# SCH_PCB-micropad_2024-07-07.net
KiCad netlist of a schematic drawn in EasyEDA
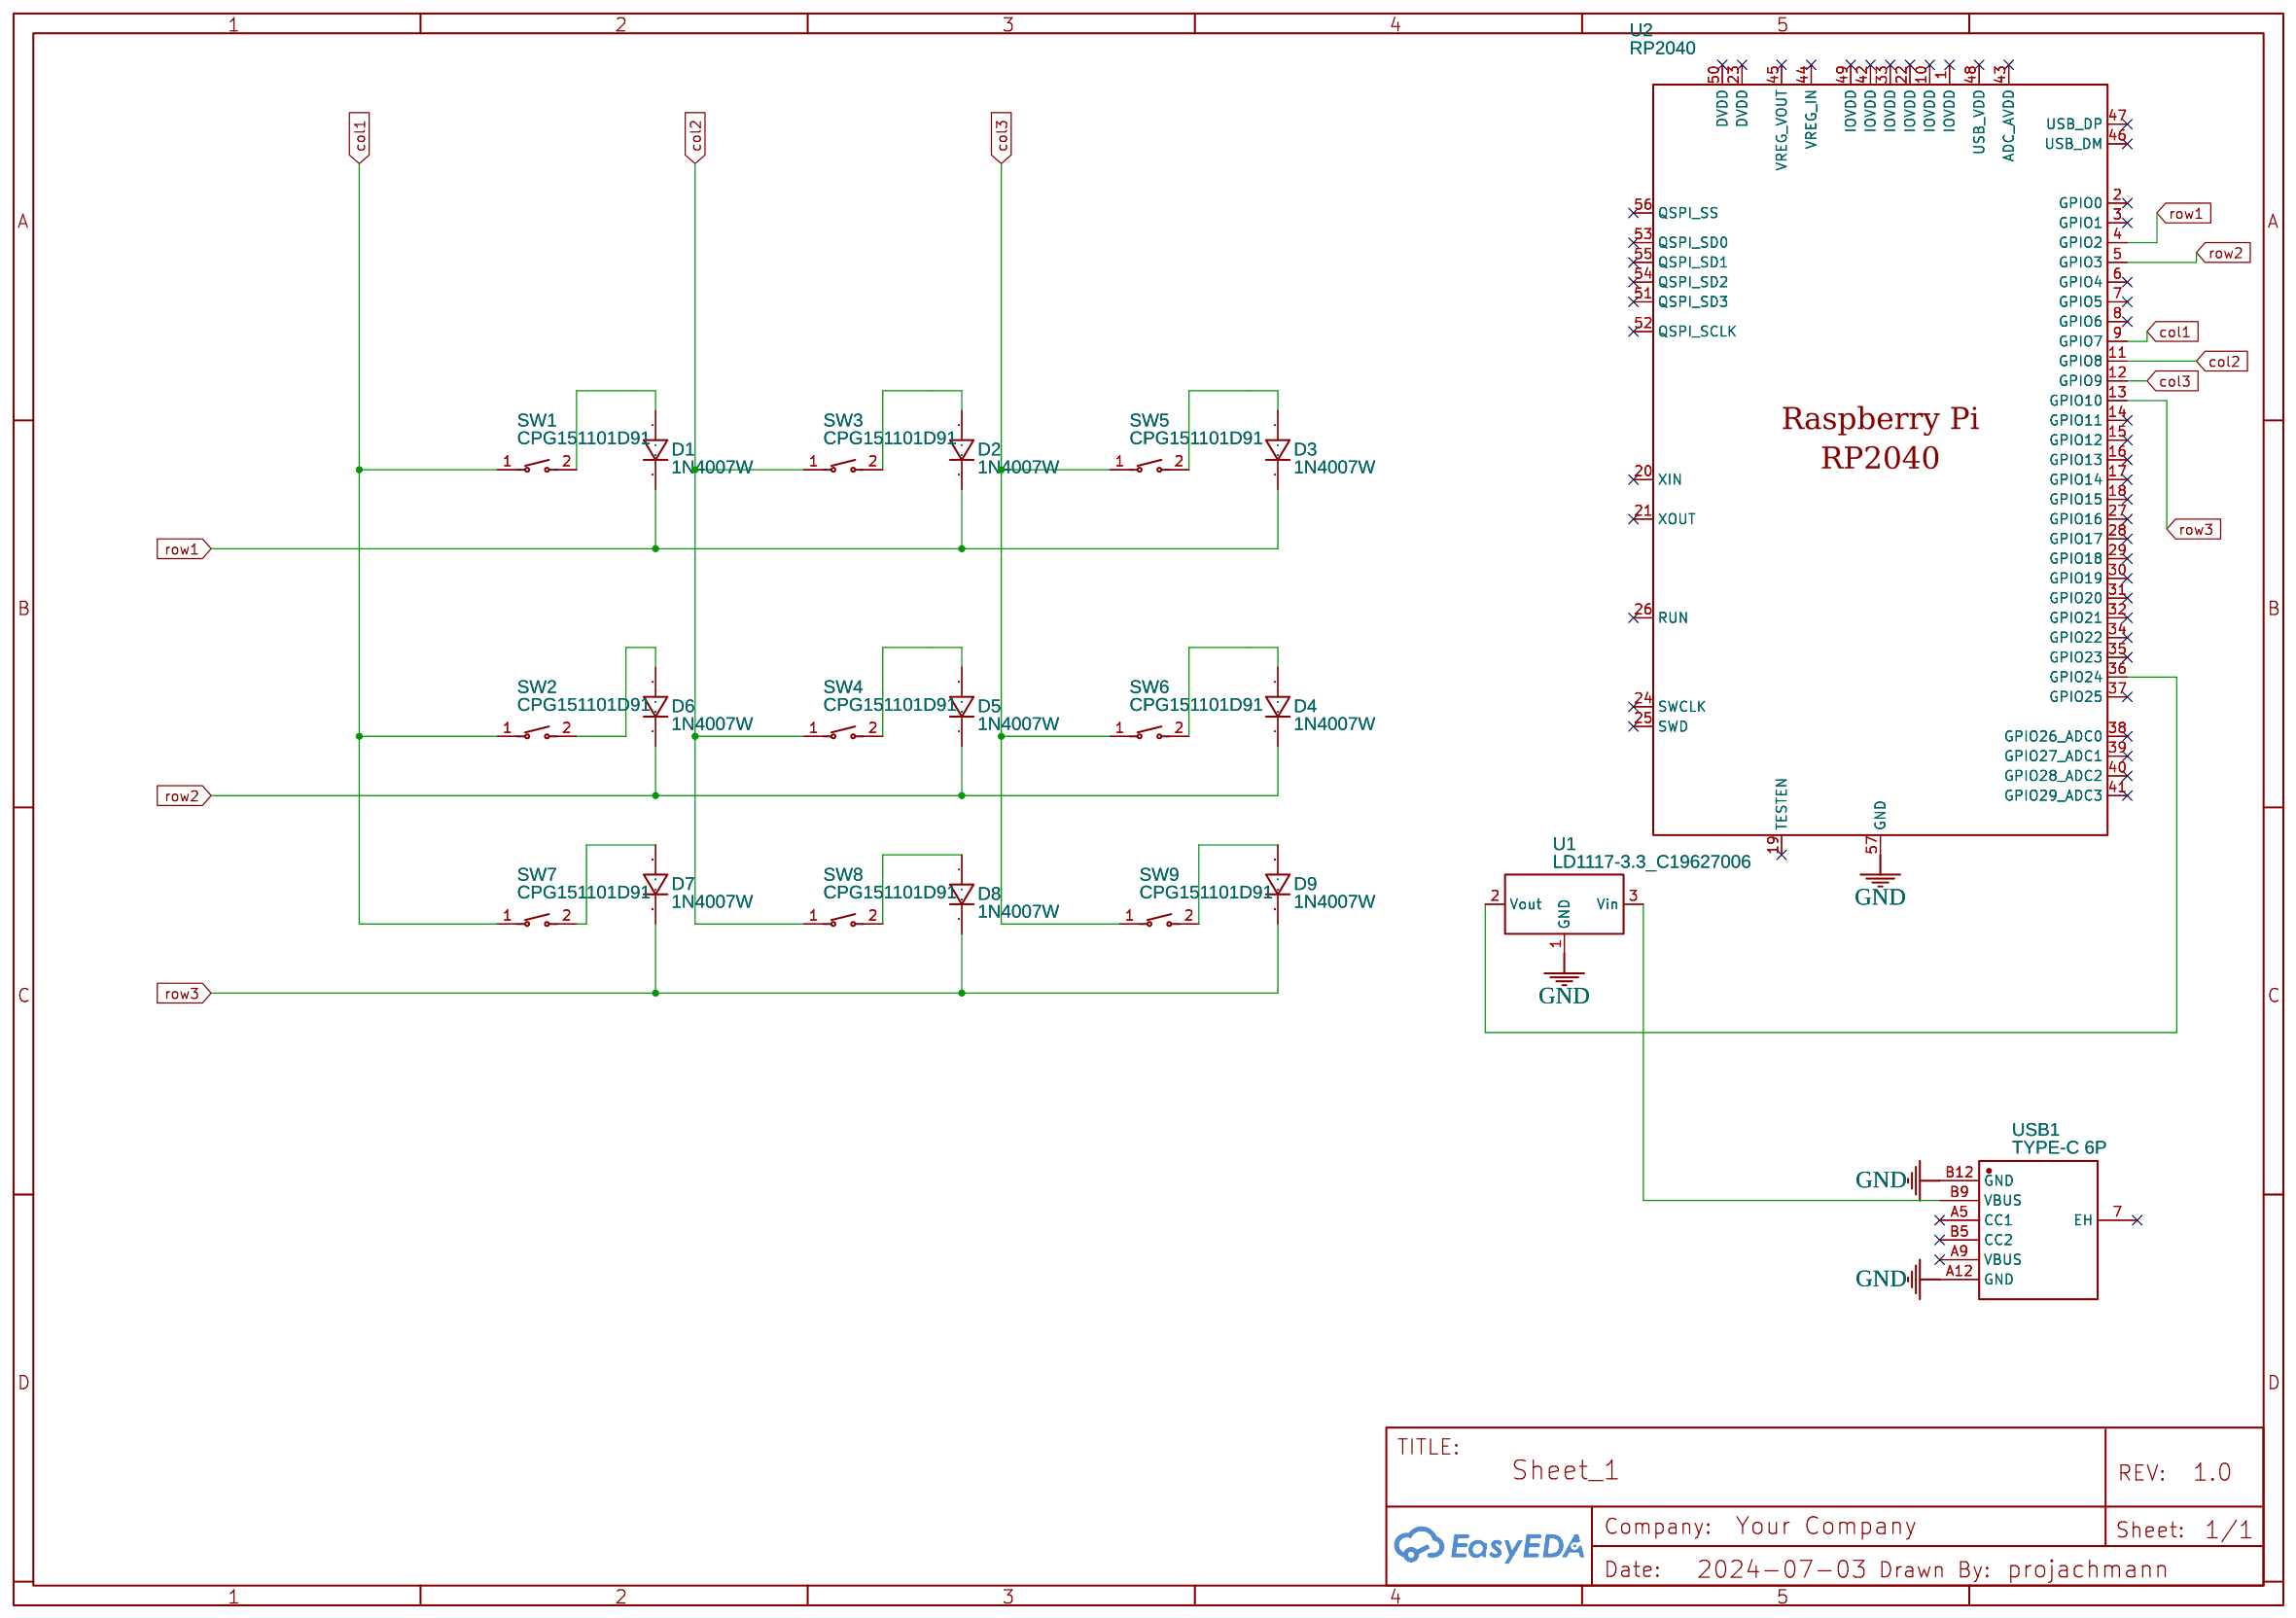
[diagram p0: schematic sheet]

(export (version "E")
  (design (tool "Eeschema 10.0.6"))
  (components
    (comp (ref "D1")
      (value "1N4007W")
      (fields (field (name "Manufacturer") "BLUE ROCKET"))
      (libsource (lib "") (part "1N4007W"))
    )
    (comp (ref "D2")
      (value "1N4007W")
      (fields (field (name "Manufacturer") "BLUE ROCKET"))
      (libsource (lib "") (part "1N4007W"))
    )
    (comp (ref "D3")
      (value "1N4007W")
      (fields (field (name "Manufacturer") "BLUE ROCKET"))
      (libsource (lib "") (part "1N4007W"))
    )
    (comp (ref "D4")
      (value "1N4007W")
      (fields (field (name "Manufacturer") "BLUE ROCKET"))
      (libsource (lib "") (part "1N4007W"))
    )
    (comp (ref "D5")
      (value "1N4007W")
      (fields (field (name "Manufacturer") "BLUE ROCKET"))
      (libsource (lib "") (part "1N4007W"))
    )
    (comp (ref "D6")
      (value "1N4007W")
      (fields (field (name "Manufacturer") "BLUE ROCKET"))
      (libsource (lib "") (part "1N4007W"))
    )
    (comp (ref "D7")
      (value "1N4007W")
      (fields (field (name "Manufacturer") "BLUE ROCKET"))
      (libsource (lib "") (part "1N4007W"))
    )
    (comp (ref "D8")
      (value "1N4007W")
      (fields (field (name "Manufacturer") "BLUE ROCKET"))
      (libsource (lib "") (part "1N4007W"))
    )
    (comp (ref "D9")
      (value "1N4007W")
      (fields (field (name "Manufacturer") "BLUE ROCKET"))
      (libsource (lib "") (part "1N4007W"))
    )
    (comp (ref "SW1")
      (value "CPG151101D91")
      (fields (field (name "Manufacturer") "Kailh(凯华)"))
      (libsource (lib "") (part "CPG151101D91"))
    )
    (comp (ref "SW2")
      (value "CPG151101D91")
      (fields (field (name "Manufacturer") "Kailh(凯华)"))
      (libsource (lib "") (part "CPG151101D91"))
    )
    (comp (ref "SW3")
      (value "CPG151101D91")
      (fields (field (name "Manufacturer") "Kailh(凯华)"))
      (libsource (lib "") (part "CPG151101D91"))
    )
    (comp (ref "SW4")
      (value "CPG151101D91")
      (fields (field (name "Manufacturer") "Kailh(凯华)"))
      (libsource (lib "") (part "CPG151101D91"))
    )
    (comp (ref "SW5")
      (value "CPG151101D91")
      (fields (field (name "Manufacturer") "Kailh(凯华)"))
      (libsource (lib "") (part "CPG151101D91"))
    )
    (comp (ref "SW6")
      (value "CPG151101D91")
      (fields (field (name "Manufacturer") "Kailh(凯华)"))
      (libsource (lib "") (part "CPG151101D91"))
    )
    (comp (ref "SW7")
      (value "CPG151101D91")
      (fields (field (name "Manufacturer") "Kailh(凯华)"))
      (libsource (lib "") (part "CPG151101D91"))
    )
    (comp (ref "SW8")
      (value "CPG151101D91")
      (fields (field (name "Manufacturer") "Kailh(凯华)"))
      (libsource (lib "") (part "CPG151101D91"))
    )
    (comp (ref "SW9")
      (value "CPG151101D91")
      (fields (field (name "Manufacturer") "Kailh(凯华)"))
      (libsource (lib "") (part "CPG151101D91"))
    )
    (comp (ref "U1")
      (value "LD1117-3.3_C19627006")
      (fields
        (field (name "Manufacturer Part") "LD1117-3.3")
        (field (name "Manufacturer") "HXY MOSFET(华轩阳电子)")
      )
      (libsource (lib "") (part "LD1117-3.3_C19627006"))
    )
    (comp (ref "U2")
      (value "RP2040")
      (fields (field (name "Manufacturer") "Raspberry Pi(树莓派)"))
      (libsource (lib "") (part "RP2040"))
    )
    (comp (ref "USB1")
      (value "TYPE-C 6P")
      (fields (field (name "Manufacturer") "SHOU HAN(首韩)"))
      (libsource (lib "") (part "TYPE-C 6P"))
    )
  )
  (nets
    (net (code "1") (name "GND") (class "Default")
      (node (ref "U1") (pin "1") (pinfunction "GND_1") (pintype "unspecified"))
      (node (ref "U2") (pin "57") (pinfunction "GND_57") (pintype "bidirectional"))
      (node (ref "USB1") (pin "A12") (pinfunction "GND_A12") (pintype "unspecified"))
      (node (ref "USB1") (pin "B12") (pinfunction "GND_B12") (pintype "unspecified"))
    )
    (net (code "2") (name "Net-(D1-Pad2)") (class "Default")
      (node (ref "D1") (pin "2") (pinfunction "2_2") (pintype "unspecified"))
      (node (ref "SW1") (pin "2") (pinfunction "2_2") (pintype "unspecified"))
    )
    (net (code "3") (name "Net-(D2-Pad2)") (class "Default")
      (node (ref "D2") (pin "2") (pinfunction "2_2") (pintype "unspecified"))
      (node (ref "SW3") (pin "2") (pinfunction "2_2") (pintype "unspecified"))
    )
    (net (code "4") (name "Net-(D3-Pad2)") (class "Default")
      (node (ref "D3") (pin "2") (pinfunction "2_2") (pintype "unspecified"))
      (node (ref "SW5") (pin "2") (pinfunction "2_2") (pintype "unspecified"))
    )
    (net (code "5") (name "Net-(D4-Pad2)") (class "Default")
      (node (ref "D4") (pin "2") (pinfunction "2_2") (pintype "unspecified"))
      (node (ref "SW6") (pin "2") (pinfunction "2_2") (pintype "unspecified"))
    )
    (net (code "6") (name "Net-(D5-Pad2)") (class "Default")
      (node (ref "D5") (pin "2") (pinfunction "2_2") (pintype "unspecified"))
      (node (ref "SW4") (pin "2") (pinfunction "2_2") (pintype "unspecified"))
    )
    (net (code "7") (name "Net-(D6-Pad2)") (class "Default")
      (node (ref "D6") (pin "2") (pinfunction "2_2") (pintype "unspecified"))
      (node (ref "SW2") (pin "2") (pinfunction "2_2") (pintype "unspecified"))
    )
    (net (code "8") (name "Net-(D7-Pad2)") (class "Default")
      (node (ref "D7") (pin "2") (pinfunction "2_2") (pintype "unspecified"))
      (node (ref "SW7") (pin "2") (pinfunction "2_2") (pintype "unspecified"))
    )
    (net (code "9") (name "Net-(D8-Pad2)") (class "Default")
      (node (ref "D8") (pin "2") (pinfunction "2_2") (pintype "unspecified"))
      (node (ref "SW8") (pin "2") (pinfunction "2_2") (pintype "unspecified"))
    )
    (net (code "10") (name "Net-(D9-Pad2)") (class "Default")
      (node (ref "D9") (pin "2") (pinfunction "2_2") (pintype "unspecified"))
      (node (ref "SW9") (pin "2") (pinfunction "2_2") (pintype "unspecified"))
    )
    (net (code "11") (name "Net-(U1-Vin)") (class "Default")
      (node (ref "U1") (pin "3") (pinfunction "Vin_3") (pintype "unspecified"))
      (node (ref "USB1") (pin "B9") (pinfunction "VBUS_B9") (pintype "unspecified"))
    )
    (net (code "12") (name "Net-(U1-Vout)") (class "Default")
      (node (ref "U1") (pin "2") (pinfunction "Vout_2") (pintype "unspecified"))
      (node (ref "U2") (pin "36") (pinfunction "GPIO24_36") (pintype "bidirectional"))
    )
    (net (code "13") (name "col1") (class "Default")
      (node (ref "SW1") (pin "1") (pinfunction "1_1") (pintype "unspecified"))
      (node (ref "SW2") (pin "1") (pinfunction "1_1") (pintype "unspecified"))
      (node (ref "SW7") (pin "1") (pinfunction "1_1") (pintype "unspecified"))
      (node (ref "U2") (pin "9") (pinfunction "GPIO7_9") (pintype "bidirectional"))
    )
    (net (code "14") (name "col2") (class "Default")
      (node (ref "SW3") (pin "1") (pinfunction "1_1") (pintype "unspecified"))
      (node (ref "SW4") (pin "1") (pinfunction "1_1") (pintype "unspecified"))
      (node (ref "SW8") (pin "1") (pinfunction "1_1") (pintype "unspecified"))
      (node (ref "U2") (pin "11") (pinfunction "GPIO8_11") (pintype "bidirectional"))
    )
    (net (code "15") (name "col3") (class "Default")
      (node (ref "SW5") (pin "1") (pinfunction "1_1") (pintype "unspecified"))
      (node (ref "SW6") (pin "1") (pinfunction "1_1") (pintype "unspecified"))
      (node (ref "SW9") (pin "1") (pinfunction "1_1") (pintype "unspecified"))
      (node (ref "U2") (pin "12") (pinfunction "GPIO9_12") (pintype "bidirectional"))
    )
    (net (code "16") (name "row1") (class "Default")
      (node (ref "D1") (pin "1") (pinfunction "1_1") (pintype "unspecified"))
      (node (ref "D2") (pin "1") (pinfunction "1_1") (pintype "unspecified"))
      (node (ref "D3") (pin "1") (pinfunction "1_1") (pintype "unspecified"))
      (node (ref "U2") (pin "4") (pinfunction "GPIO2_4") (pintype "bidirectional"))
    )
    (net (code "17") (name "row2") (class "Default")
      (node (ref "D4") (pin "1") (pinfunction "1_1") (pintype "unspecified"))
      (node (ref "D5") (pin "1") (pinfunction "1_1") (pintype "unspecified"))
      (node (ref "D6") (pin "1") (pinfunction "1_1") (pintype "unspecified"))
      (node (ref "U2") (pin "5") (pinfunction "GPIO3_5") (pintype "bidirectional"))
    )
    (net (code "18") (name "row3") (class "Default")
      (node (ref "D7") (pin "1") (pinfunction "1_1") (pintype "unspecified"))
      (node (ref "D8") (pin "1") (pinfunction "1_1") (pintype "unspecified"))
      (node (ref "D9") (pin "1") (pinfunction "1_1") (pintype "unspecified"))
      (node (ref "U2") (pin "13") (pinfunction "GPIO10_13") (pintype "bidirectional"))
    )
    (net (code "19") (name "unconnected-(U2-ADC_AVDD-Pad43)") (class "Default")
      (node (ref "U2") (pin "43") (pinfunction "ADC_AVDD_43") (pintype "bidirectional+no_connect"))
    )
    (net (code "20") (name "unconnected-(U2-DVDD-Pad23)") (class "Default")
      (node (ref "U2") (pin "23") (pinfunction "DVDD_23") (pintype "bidirectional+no_connect"))
    )
    (net (code "21") (name "unconnected-(U2-DVDD-Pad50)") (class "Default")
      (node (ref "U2") (pin "50") (pinfunction "DVDD_50") (pintype "bidirectional+no_connect"))
    )
    (net (code "22") (name "unconnected-(U2-GPIO0-Pad2)") (class "Default")
      (node (ref "U2") (pin "2") (pinfunction "GPIO0_2") (pintype "bidirectional+no_connect"))
    )
    (net (code "23") (name "unconnected-(U2-GPIO1-Pad3)") (class "Default")
      (node (ref "U2") (pin "3") (pinfunction "GPIO1_3") (pintype "bidirectional+no_connect"))
    )
    (net (code "24") (name "unconnected-(U2-GPIO4-Pad6)") (class "Default")
      (node (ref "U2") (pin "6") (pinfunction "GPIO4_6") (pintype "bidirectional+no_connect"))
    )
    (net (code "25") (name "unconnected-(U2-GPIO5-Pad7)") (class "Default")
      (node (ref "U2") (pin "7") (pinfunction "GPIO5_7") (pintype "bidirectional+no_connect"))
    )
    (net (code "26") (name "unconnected-(U2-GPIO6-Pad8)") (class "Default")
      (node (ref "U2") (pin "8") (pinfunction "GPIO6_8") (pintype "bidirectional+no_connect"))
    )
    (net (code "27") (name "unconnected-(U2-GPIO11-Pad14)") (class "Default")
      (node (ref "U2") (pin "14") (pinfunction "GPIO11_14") (pintype "bidirectional+no_connect"))
    )
    (net (code "28") (name "unconnected-(U2-GPIO12-Pad15)") (class "Default")
      (node (ref "U2") (pin "15") (pinfunction "GPIO12_15") (pintype "bidirectional+no_connect"))
    )
    (net (code "29") (name "unconnected-(U2-GPIO13-Pad16)") (class "Default")
      (node (ref "U2") (pin "16") (pinfunction "GPIO13_16") (pintype "bidirectional+no_connect"))
    )
    (net (code "30") (name "unconnected-(U2-GPIO14-Pad17)") (class "Default")
      (node (ref "U2") (pin "17") (pinfunction "GPIO14_17") (pintype "bidirectional+no_connect"))
    )
    (net (code "31") (name "unconnected-(U2-GPIO15-Pad18)") (class "Default")
      (node (ref "U2") (pin "18") (pinfunction "GPIO15_18") (pintype "bidirectional+no_connect"))
    )
    (net (code "32") (name "unconnected-(U2-GPIO16-Pad27)") (class "Default")
      (node (ref "U2") (pin "27") (pinfunction "GPIO16_27") (pintype "bidirectional+no_connect"))
    )
    (net (code "33") (name "unconnected-(U2-GPIO17-Pad28)") (class "Default")
      (node (ref "U2") (pin "28") (pinfunction "GPIO17_28") (pintype "bidirectional+no_connect"))
    )
    (net (code "34") (name "unconnected-(U2-GPIO18-Pad29)") (class "Default")
      (node (ref "U2") (pin "29") (pinfunction "GPIO18_29") (pintype "bidirectional+no_connect"))
    )
    (net (code "35") (name "unconnected-(U2-GPIO19-Pad30)") (class "Default")
      (node (ref "U2") (pin "30") (pinfunction "GPIO19_30") (pintype "bidirectional+no_connect"))
    )
    (net (code "36") (name "unconnected-(U2-GPIO20-Pad31)") (class "Default")
      (node (ref "U2") (pin "31") (pinfunction "GPIO20_31") (pintype "bidirectional+no_connect"))
    )
    (net (code "37") (name "unconnected-(U2-GPIO21-Pad32)") (class "Default")
      (node (ref "U2") (pin "32") (pinfunction "GPIO21_32") (pintype "bidirectional+no_connect"))
    )
    (net (code "38") (name "unconnected-(U2-GPIO22-Pad34)") (class "Default")
      (node (ref "U2") (pin "34") (pinfunction "GPIO22_34") (pintype "bidirectional+no_connect"))
    )
    (net (code "39") (name "unconnected-(U2-GPIO23-Pad35)") (class "Default")
      (node (ref "U2") (pin "35") (pinfunction "GPIO23_35") (pintype "bidirectional+no_connect"))
    )
    (net (code "40") (name "unconnected-(U2-GPIO25-Pad37)") (class "Default")
      (node (ref "U2") (pin "37") (pinfunction "GPIO25_37") (pintype "bidirectional+no_connect"))
    )
    (net (code "41") (name "unconnected-(U2-GPIO26_ADC0-Pad38)") (class "Default")
      (node (ref "U2") (pin "38") (pinfunction "GPIO26_ADC0_38") (pintype "bidirectional+no_connect"))
    )
    (net (code "42") (name "unconnected-(U2-GPIO27_ADC1-Pad39)") (class "Default")
      (node (ref "U2") (pin "39") (pinfunction "GPIO27_ADC1_39") (pintype "bidirectional+no_connect"))
    )
    (net (code "43") (name "unconnected-(U2-GPIO28_ADC2-Pad40)") (class "Default")
      (node (ref "U2") (pin "40") (pinfunction "GPIO28_ADC2_40") (pintype "bidirectional+no_connect"))
    )
    (net (code "44") (name "unconnected-(U2-GPIO29_ADC3-Pad41)") (class "Default")
      (node (ref "U2") (pin "41") (pinfunction "GPIO29_ADC3_41") (pintype "bidirectional+no_connect"))
    )
    (net (code "45") (name "unconnected-(U2-IOVDD-Pad1)") (class "Default")
      (node (ref "U2") (pin "1") (pinfunction "IOVDD_1") (pintype "bidirectional+no_connect"))
    )
    (net (code "46") (name "unconnected-(U2-IOVDD-Pad10)") (class "Default")
      (node (ref "U2") (pin "10") (pinfunction "IOVDD_10") (pintype "bidirectional+no_connect"))
    )
    (net (code "47") (name "unconnected-(U2-IOVDD-Pad22)") (class "Default")
      (node (ref "U2") (pin "22") (pinfunction "IOVDD_22") (pintype "bidirectional+no_connect"))
    )
    (net (code "48") (name "unconnected-(U2-IOVDD-Pad33)") (class "Default")
      (node (ref "U2") (pin "33") (pinfunction "IOVDD_33") (pintype "bidirectional+no_connect"))
    )
    (net (code "49") (name "unconnected-(U2-IOVDD-Pad42)") (class "Default")
      (node (ref "U2") (pin "42") (pinfunction "IOVDD_42") (pintype "bidirectional+no_connect"))
    )
    (net (code "50") (name "unconnected-(U2-IOVDD-Pad49)") (class "Default")
      (node (ref "U2") (pin "49") (pinfunction "IOVDD_49") (pintype "bidirectional+no_connect"))
    )
    (net (code "51") (name "unconnected-(U2-QSPI_SCLK-Pad52)") (class "Default")
      (node (ref "U2") (pin "52") (pinfunction "QSPI_SCLK_52") (pintype "output+no_connect"))
    )
    (net (code "52") (name "unconnected-(U2-QSPI_SD0-Pad53)") (class "Default")
      (node (ref "U2") (pin "53") (pinfunction "QSPI_SD0_53") (pintype "bidirectional+no_connect"))
    )
    (net (code "53") (name "unconnected-(U2-QSPI_SD1-Pad55)") (class "Default")
      (node (ref "U2") (pin "55") (pinfunction "QSPI_SD1_55") (pintype "bidirectional+no_connect"))
    )
    (net (code "54") (name "unconnected-(U2-QSPI_SD2-Pad54)") (class "Default")
      (node (ref "U2") (pin "54") (pinfunction "QSPI_SD2_54") (pintype "bidirectional+no_connect"))
    )
    (net (code "55") (name "unconnected-(U2-QSPI_SD3-Pad51)") (class "Default")
      (node (ref "U2") (pin "51") (pinfunction "QSPI_SD3_51") (pintype "bidirectional+no_connect"))
    )
    (net (code "56") (name "unconnected-(U2-QSPI_SS-Pad56)") (class "Default")
      (node (ref "U2") (pin "56") (pinfunction "QSPI_SS_56") (pintype "bidirectional+no_connect"))
    )
    (net (code "57") (name "unconnected-(U2-RUN-Pad26)") (class "Default")
      (node (ref "U2") (pin "26") (pinfunction "RUN_26") (pintype "input+no_connect"))
    )
    (net (code "58") (name "unconnected-(U2-SWCLK-Pad24)") (class "Default")
      (node (ref "U2") (pin "24") (pinfunction "SWCLK_24") (pintype "output+no_connect"))
    )
    (net (code "59") (name "unconnected-(U2-SWD-Pad25)") (class "Default")
      (node (ref "U2") (pin "25") (pinfunction "SWD_25") (pintype "bidirectional+no_connect"))
    )
    (net (code "60") (name "unconnected-(U2-TESTEN-Pad19)") (class "Default")
      (node (ref "U2") (pin "19") (pinfunction "TESTEN_19") (pintype "unspecified+no_connect"))
    )
    (net (code "61") (name "unconnected-(U2-USB_DM-Pad46)") (class "Default")
      (node (ref "U2") (pin "46") (pinfunction "USB_DM_46") (pintype "bidirectional+no_connect"))
    )
    (net (code "62") (name "unconnected-(U2-USB_DP-Pad47)") (class "Default")
      (node (ref "U2") (pin "47") (pinfunction "USB_DP_47") (pintype "bidirectional+no_connect"))
    )
    (net (code "63") (name "unconnected-(U2-USB_VDD-Pad48)") (class "Default")
      (node (ref "U2") (pin "48") (pinfunction "USB_VDD_48") (pintype "bidirectional+no_connect"))
    )
    (net (code "64") (name "unconnected-(U2-VREG_IN-Pad44)") (class "Default")
      (node (ref "U2") (pin "44") (pinfunction "VREG_IN_44") (pintype "bidirectional+no_connect"))
    )
    (net (code "65") (name "unconnected-(U2-VREG_VOUT-Pad45)") (class "Default")
      (node (ref "U2") (pin "45") (pinfunction "VREG_VOUT_45") (pintype "bidirectional+no_connect"))
    )
    (net (code "66") (name "unconnected-(U2-XIN-Pad20)") (class "Default")
      (node (ref "U2") (pin "20") (pinfunction "XIN_20") (pintype "input+no_connect"))
    )
    (net (code "67") (name "unconnected-(U2-XOUT-Pad21)") (class "Default")
      (node (ref "U2") (pin "21") (pinfunction "XOUT_21") (pintype "unspecified+no_connect"))
    )
    (net (code "68") (name "unconnected-(USB1-CC1-PadA5)") (class "Default")
      (node (ref "USB1") (pin "A5") (pinfunction "CC1_A5") (pintype "unspecified+no_connect"))
    )
    (net (code "69") (name "unconnected-(USB1-CC2-PadB5)") (class "Default")
      (node (ref "USB1") (pin "B5") (pinfunction "CC2_B5") (pintype "unspecified+no_connect"))
    )
    (net (code "70") (name "unconnected-(USB1-EH-Pad7)") (class "Default")
      (node (ref "USB1") (pin "7") (pinfunction "EH_7") (pintype "unspecified+no_connect"))
    )
    (net (code "71") (name "unconnected-(USB1-VBUS-PadA9)") (class "Default")
      (node (ref "USB1") (pin "A9") (pinfunction "VBUS_A9") (pintype "unspecified+no_connect"))
    )
  )
)
